# working.net
KiCad netlist of a schematic drawn in EAGLE
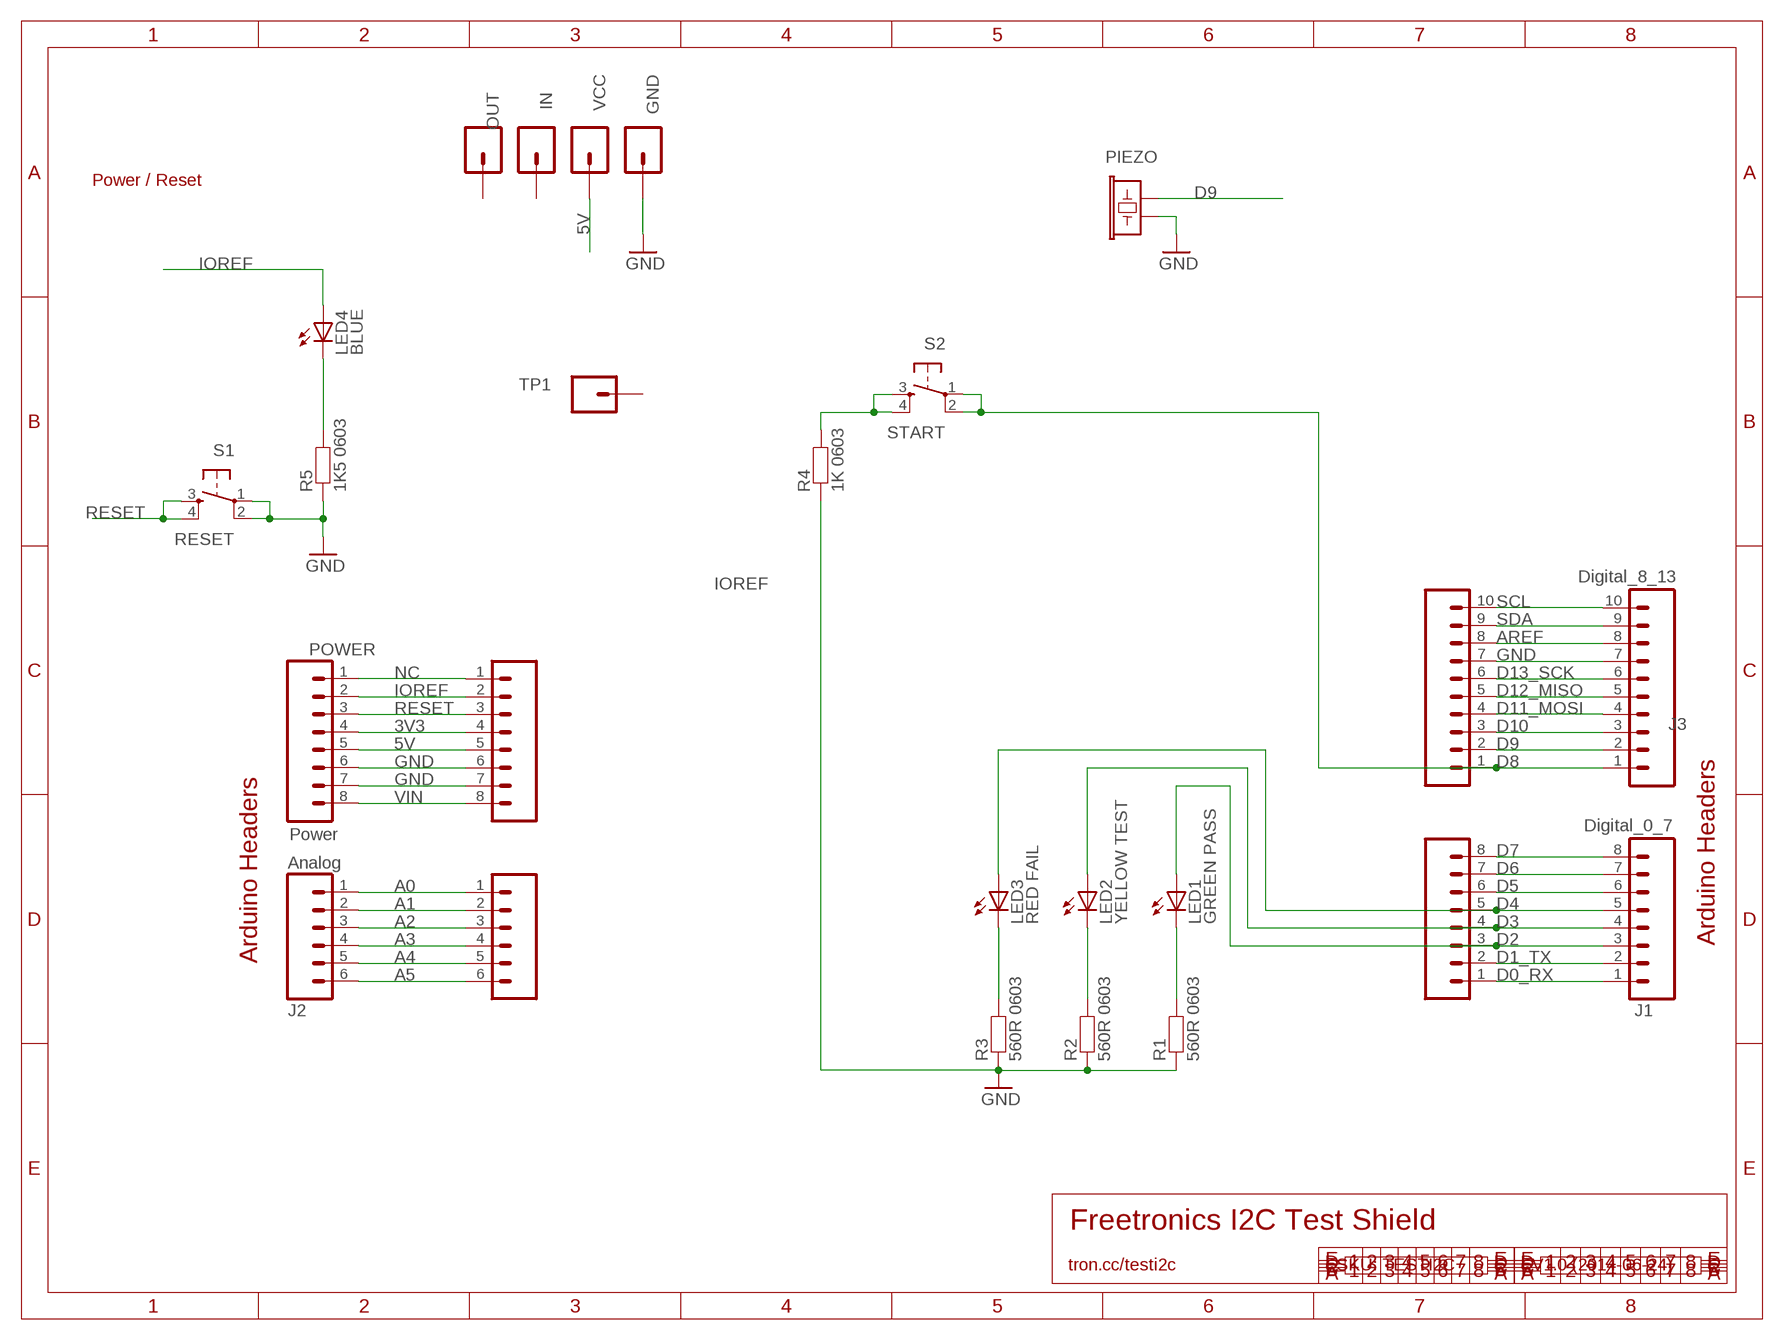
[diagram p0: schematic, sheet 1]

(export (version "E")
  (design (tool "Eeschema 10.0.6"))
  (components
    (comp (ref "GND")
      (value "M01PTH")
      (footprint "eagle-import:1X01")
      (libsource (lib "eagle-import") (part "M01PTH"))
    )
    (comp (ref "IN")
      (value "M01PTH")
      (footprint "eagle-import:1X01")
      (libsource (lib "eagle-import") (part "M01PTH"))
    )
    (comp (ref "J1")
      (value "Digital_0_7")
      (footprint "eagle-import:1X08")
      (libsource (lib "eagle-import") (part "M08"))
    )
    (comp (ref "J2")
      (value "Analog")
      (footprint "eagle-import:1X06")
      (libsource (lib "eagle-import") (part "M06SIP"))
    )
    (comp (ref "J3")
      (value "Digital_8_13")
      (footprint "eagle-import:1X10")
      (libsource (lib "eagle-import") (part "M100.1"))
    )
    (comp (ref "LED1")
      (value "GREEN PASS")
      (footprint "eagle-import:LED-0603")
      (libsource (lib "eagle-import") (part "LED0603"))
    )
    (comp (ref "LED2")
      (value "YELLOW TEST")
      (footprint "eagle-import:LED-0603")
      (libsource (lib "eagle-import") (part "LED0603"))
    )
    (comp (ref "LED3")
      (value "RED FAIL")
      (footprint "eagle-import:LED-0603")
      (libsource (lib "eagle-import") (part "LED0603"))
    )
    (comp (ref "LED4")
      (value "BLUE")
      (footprint "eagle-import:LED-0603")
      (libsource (lib "eagle-import") (part "LED0603"))
    )
    (comp (ref "OUT")
      (value "M01PTH")
      (footprint "eagle-import:1X01")
      (libsource (lib "eagle-import") (part "M01PTH"))
    )
    (comp (ref "PIEZO")
      (value "BUZZERSMD12X12")
      (footprint "eagle-import:BUZZER-12X12-SMT")
      (libsource (lib "eagle-import") (part "BUZZERSMD12X12"))
    )
    (comp (ref "POWER")
      (value "Power")
      (footprint "eagle-import:1X08")
      (libsource (lib "eagle-import") (part "M08"))
    )
    (comp (ref "R1")
      (value "560R 0603")
      (footprint "eagle-import:0603")
      (libsource (lib "eagle-import") (part "RESISTOR0603"))
    )
    (comp (ref "R2")
      (value "560R 0603")
      (footprint "eagle-import:0603")
      (libsource (lib "eagle-import") (part "RESISTOR0603"))
    )
    (comp (ref "R3")
      (value "560R 0603")
      (footprint "eagle-import:0603")
      (libsource (lib "eagle-import") (part "RESISTOR0603"))
    )
    (comp (ref "R4")
      (value "1K 0603")
      (footprint "eagle-import:0603")
      (libsource (lib "eagle-import") (part "RESISTOR0603"))
    )
    (comp (ref "R5")
      (value "1K5 0603")
      (footprint "eagle-import:0603")
      (libsource (lib "eagle-import") (part "RESISTOR0603"))
    )
    (comp (ref "S1")
      (value "RESET")
      (footprint "eagle-import:TACTILE-PTH")
      (libsource (lib "eagle-import") (part "TAC_SWITCHPTH"))
    )
    (comp (ref "S2")
      (value "START")
      (footprint "eagle-import:TACTILE-PTH")
      (libsource (lib "eagle-import") (part "TAC_SWITCHPTH"))
    )
    (comp (ref "SL1")
      (value "Digital_0_7")
      (footprint "eagle-import:1X08")
      (libsource (lib "eagle-import") (part "M08"))
    )
    (comp (ref "SL2")
      (value "Analog")
      (footprint "eagle-import:1X06")
      (libsource (lib "eagle-import") (part "M06SIP"))
    )
    (comp (ref "SL3")
      (value "Digital_8_13")
      (footprint "eagle-import:1X10")
      (libsource (lib "eagle-import") (part "M100.1"))
    )
    (comp (ref "SLP")
      (value "Power")
      (footprint "eagle-import:1X08")
      (libsource (lib "eagle-import") (part "M08"))
    )
    (comp (ref "TP1")
      (value "M01PTH")
      (footprint "eagle-import:1X01")
      (libsource (lib "eagle-import") (part "M01PTH"))
    )
    (comp (ref "VCC")
      (value "M01PTH")
      (footprint "eagle-import:1X01")
      (libsource (lib "eagle-import") (part "M01PTH"))
    )
  )
  (nets
    (net (code "1") (name "/3V3") (class "Default")
      (node (ref "POWER") (pin "4") (pinfunction "4_4") (pintype "passive"))
      (node (ref "SLP") (pin "4") (pinfunction "4_4") (pintype "passive"))
    )
    (net (code "2") (name "/5V") (class "Default")
      (node (ref "POWER") (pin "5") (pinfunction "5_5") (pintype "passive"))
      (node (ref "SLP") (pin "5") (pinfunction "5_5") (pintype "passive"))
      (node (ref "VCC") (pin "1") (pinfunction "1_1") (pintype "passive"))
    )
    (net (code "3") (name "/A0") (class "Default")
      (node (ref "J2") (pin "1") (pinfunction "1_1") (pintype "passive"))
      (node (ref "SL2") (pin "1") (pinfunction "1_1") (pintype "passive"))
    )
    (net (code "4") (name "/A1") (class "Default")
      (node (ref "J2") (pin "2") (pinfunction "2_2") (pintype "passive"))
      (node (ref "SL2") (pin "2") (pinfunction "2_2") (pintype "passive"))
    )
    (net (code "5") (name "/A2") (class "Default")
      (node (ref "J2") (pin "3") (pinfunction "3_3") (pintype "passive"))
      (node (ref "SL2") (pin "3") (pinfunction "3_3") (pintype "passive"))
    )
    (net (code "6") (name "/A3") (class "Default")
      (node (ref "J2") (pin "4") (pinfunction "4_4") (pintype "passive"))
      (node (ref "SL2") (pin "4") (pinfunction "4_4") (pintype "passive"))
    )
    (net (code "7") (name "/A4") (class "Default")
      (node (ref "J2") (pin "5") (pinfunction "5_5") (pintype "passive"))
      (node (ref "SL2") (pin "5") (pinfunction "5_5") (pintype "passive"))
    )
    (net (code "8") (name "/A5") (class "Default")
      (node (ref "J2") (pin "6") (pinfunction "6_6") (pintype "passive"))
      (node (ref "SL2") (pin "6") (pinfunction "6_6") (pintype "passive"))
    )
    (net (code "9") (name "/AREF") (class "Default")
      (node (ref "J3") (pin "8") (pinfunction "8_8") (pintype "passive"))
      (node (ref "SL3") (pin "8") (pinfunction "8_8") (pintype "passive"))
    )
    (net (code "10") (name "/D0_RX") (class "Default")
      (node (ref "J1") (pin "1") (pinfunction "1_1") (pintype "passive"))
      (node (ref "SL1") (pin "1") (pinfunction "1_1") (pintype "passive"))
    )
    (net (code "11") (name "/D1_TX") (class "Default")
      (node (ref "J1") (pin "2") (pinfunction "2_2") (pintype "passive"))
      (node (ref "SL1") (pin "2") (pinfunction "2_2") (pintype "passive"))
    )
    (net (code "12") (name "/D2") (class "Default")
      (node (ref "J1") (pin "3") (pinfunction "3_3") (pintype "passive"))
      (node (ref "LED1") (pin "A") (pinfunction "A_A") (pintype "passive"))
      (node (ref "SL1") (pin "3") (pinfunction "3_3") (pintype "passive"))
    )
    (net (code "13") (name "/D3") (class "Default")
      (node (ref "J1") (pin "4") (pinfunction "4_4") (pintype "passive"))
      (node (ref "LED2") (pin "A") (pinfunction "A_A") (pintype "passive"))
      (node (ref "SL1") (pin "4") (pinfunction "4_4") (pintype "passive"))
    )
    (net (code "14") (name "/D4") (class "Default")
      (node (ref "J1") (pin "5") (pinfunction "5_5") (pintype "passive"))
      (node (ref "LED3") (pin "A") (pinfunction "A_A") (pintype "passive"))
      (node (ref "SL1") (pin "5") (pinfunction "5_5") (pintype "passive"))
    )
    (net (code "15") (name "/D5") (class "Default")
      (node (ref "J1") (pin "6") (pinfunction "6_6") (pintype "passive"))
      (node (ref "SL1") (pin "6") (pinfunction "6_6") (pintype "passive"))
    )
    (net (code "16") (name "/D6") (class "Default")
      (node (ref "J1") (pin "7") (pinfunction "7_7") (pintype "passive"))
      (node (ref "SL1") (pin "7") (pinfunction "7_7") (pintype "passive"))
    )
    (net (code "17") (name "/D7") (class "Default")
      (node (ref "J1") (pin "8") (pinfunction "8_8") (pintype "passive"))
      (node (ref "SL1") (pin "8") (pinfunction "8_8") (pintype "passive"))
    )
    (net (code "18") (name "/D8") (class "Default")
      (node (ref "J3") (pin "1") (pinfunction "1_1") (pintype "passive"))
      (node (ref "S2") (pin "1") (pinfunction "1_1") (pintype "passive"))
      (node (ref "S2") (pin "2") (pinfunction "2_2") (pintype "passive"))
      (node (ref "SL3") (pin "1") (pinfunction "1_1") (pintype "passive"))
    )
    (net (code "19") (name "/D9") (class "Default")
      (node (ref "J3") (pin "2") (pinfunction "2_2") (pintype "passive"))
      (node (ref "PIEZO") (pin "2") (pinfunction "2_2") (pintype "passive"))
      (node (ref "SL3") (pin "2") (pinfunction "2_2") (pintype "passive"))
    )
    (net (code "20") (name "/D10") (class "Default")
      (node (ref "J3") (pin "3") (pinfunction "3_3") (pintype "passive"))
      (node (ref "SL3") (pin "3") (pinfunction "3_3") (pintype "passive"))
    )
    (net (code "21") (name "/D11_MOSI") (class "Default")
      (node (ref "J3") (pin "4") (pinfunction "4_4") (pintype "passive"))
      (node (ref "SL3") (pin "4") (pinfunction "4_4") (pintype "passive"))
    )
    (net (code "22") (name "/D12_MISO") (class "Default")
      (node (ref "J3") (pin "5") (pinfunction "5_5") (pintype "passive"))
      (node (ref "SL3") (pin "5") (pinfunction "5_5") (pintype "passive"))
    )
    (net (code "23") (name "/D13_SCK") (class "Default")
      (node (ref "J3") (pin "6") (pinfunction "6_6") (pintype "passive"))
      (node (ref "SL3") (pin "6") (pinfunction "6_6") (pintype "passive"))
    )
    (net (code "24") (name "/IOREF") (class "Default")
      (node (ref "LED4") (pin "A") (pinfunction "A_A") (pintype "passive"))
      (node (ref "POWER") (pin "2") (pinfunction "2_2") (pintype "passive"))
      (node (ref "SLP") (pin "2") (pinfunction "2_2") (pintype "passive"))
    )
    (net (code "25") (name "/NC") (class "Default")
      (node (ref "POWER") (pin "1") (pinfunction "1_1") (pintype "passive"))
      (node (ref "SLP") (pin "1") (pinfunction "1_1") (pintype "passive"))
    )
    (net (code "26") (name "/RESET") (class "Default")
      (node (ref "POWER") (pin "3") (pinfunction "3_3") (pintype "passive"))
      (node (ref "S1") (pin "3") (pinfunction "3_3") (pintype "passive"))
      (node (ref "S1") (pin "4") (pinfunction "4_4") (pintype "passive"))
      (node (ref "SLP") (pin "3") (pinfunction "3_3") (pintype "passive"))
    )
    (net (code "27") (name "/SCL") (class "Default")
      (node (ref "J3") (pin "10") (pinfunction "10_10") (pintype "passive"))
      (node (ref "SL3") (pin "10") (pinfunction "10_10") (pintype "passive"))
    )
    (net (code "28") (name "/SDA") (class "Default")
      (node (ref "J3") (pin "9") (pinfunction "9_9") (pintype "passive"))
      (node (ref "SL3") (pin "9") (pinfunction "9_9") (pintype "passive"))
    )
    (net (code "29") (name "/VIN") (class "Default")
      (node (ref "POWER") (pin "8") (pinfunction "8_8") (pintype "passive"))
      (node (ref "SLP") (pin "8") (pinfunction "8_8") (pintype "passive"))
    )
    (net (code "30") (name "GND") (class "Default")
      (node (ref "GND") (pin "1") (pinfunction "1_1") (pintype "passive"))
      (node (ref "J3") (pin "7") (pinfunction "7_7") (pintype "passive"))
      (node (ref "PIEZO") (pin "1") (pinfunction "1_1") (pintype "passive"))
      (node (ref "POWER") (pin "6") (pinfunction "6_6") (pintype "passive"))
      (node (ref "POWER") (pin "7") (pinfunction "7_7") (pintype "passive"))
      (node (ref "R1") (pin "1") (pinfunction "1_1") (pintype "passive"))
      (node (ref "R2") (pin "1") (pinfunction "1_1") (pintype "passive"))
      (node (ref "R3") (pin "1") (pinfunction "1_1") (pintype "passive"))
      (node (ref "R4") (pin "1") (pinfunction "1_1") (pintype "passive"))
      (node (ref "R5") (pin "1") (pinfunction "1_1") (pintype "passive"))
      (node (ref "S1") (pin "1") (pinfunction "1_1") (pintype "passive"))
      (node (ref "S1") (pin "2") (pinfunction "2_2") (pintype "passive"))
      (node (ref "SL3") (pin "7") (pinfunction "7_7") (pintype "passive"))
      (node (ref "SLP") (pin "6") (pinfunction "6_6") (pintype "passive"))
      (node (ref "SLP") (pin "7") (pinfunction "7_7") (pintype "passive"))
    )
    (net (code "31") (name "Net-(LED1-PadC)") (class "Default")
      (node (ref "LED1") (pin "C") (pinfunction "C_C") (pintype "passive"))
      (node (ref "R1") (pin "2") (pinfunction "2_2") (pintype "passive"))
    )
    (net (code "32") (name "Net-(LED2-PadC)") (class "Default")
      (node (ref "LED2") (pin "C") (pinfunction "C_C") (pintype "passive"))
      (node (ref "R2") (pin "2") (pinfunction "2_2") (pintype "passive"))
    )
    (net (code "33") (name "Net-(LED3-PadC)") (class "Default")
      (node (ref "LED3") (pin "C") (pinfunction "C_C") (pintype "passive"))
      (node (ref "R3") (pin "2") (pinfunction "2_2") (pintype "passive"))
    )
    (net (code "34") (name "Net-(LED4-PadC)") (class "Default")
      (node (ref "LED4") (pin "C") (pinfunction "C_C") (pintype "passive"))
      (node (ref "R5") (pin "2") (pinfunction "2_2") (pintype "passive"))
    )
    (net (code "35") (name "Net-(R4-Pad2)") (class "Default")
      (node (ref "R4") (pin "2") (pinfunction "2_2") (pintype "passive"))
      (node (ref "S2") (pin "3") (pinfunction "3_3") (pintype "passive"))
      (node (ref "S2") (pin "4") (pinfunction "4_4") (pintype "passive"))
    )
    (net (code "36") (name "unconnected-(IN-Pad1)") (class "Default")
      (node (ref "IN") (pin "1") (pinfunction "1_1") (pintype "passive"))
    )
    (net (code "37") (name "unconnected-(OUT-Pad1)") (class "Default")
      (node (ref "OUT") (pin "1") (pinfunction "1_1") (pintype "passive"))
    )
    (net (code "38") (name "unconnected-(TP1-Pad1)") (class "Default")
      (node (ref "TP1") (pin "1") (pinfunction "1_1") (pintype "passive"))
    )
  )
)
